# smd_2.net
KiCad netlist of a schematic drawn in EAGLE
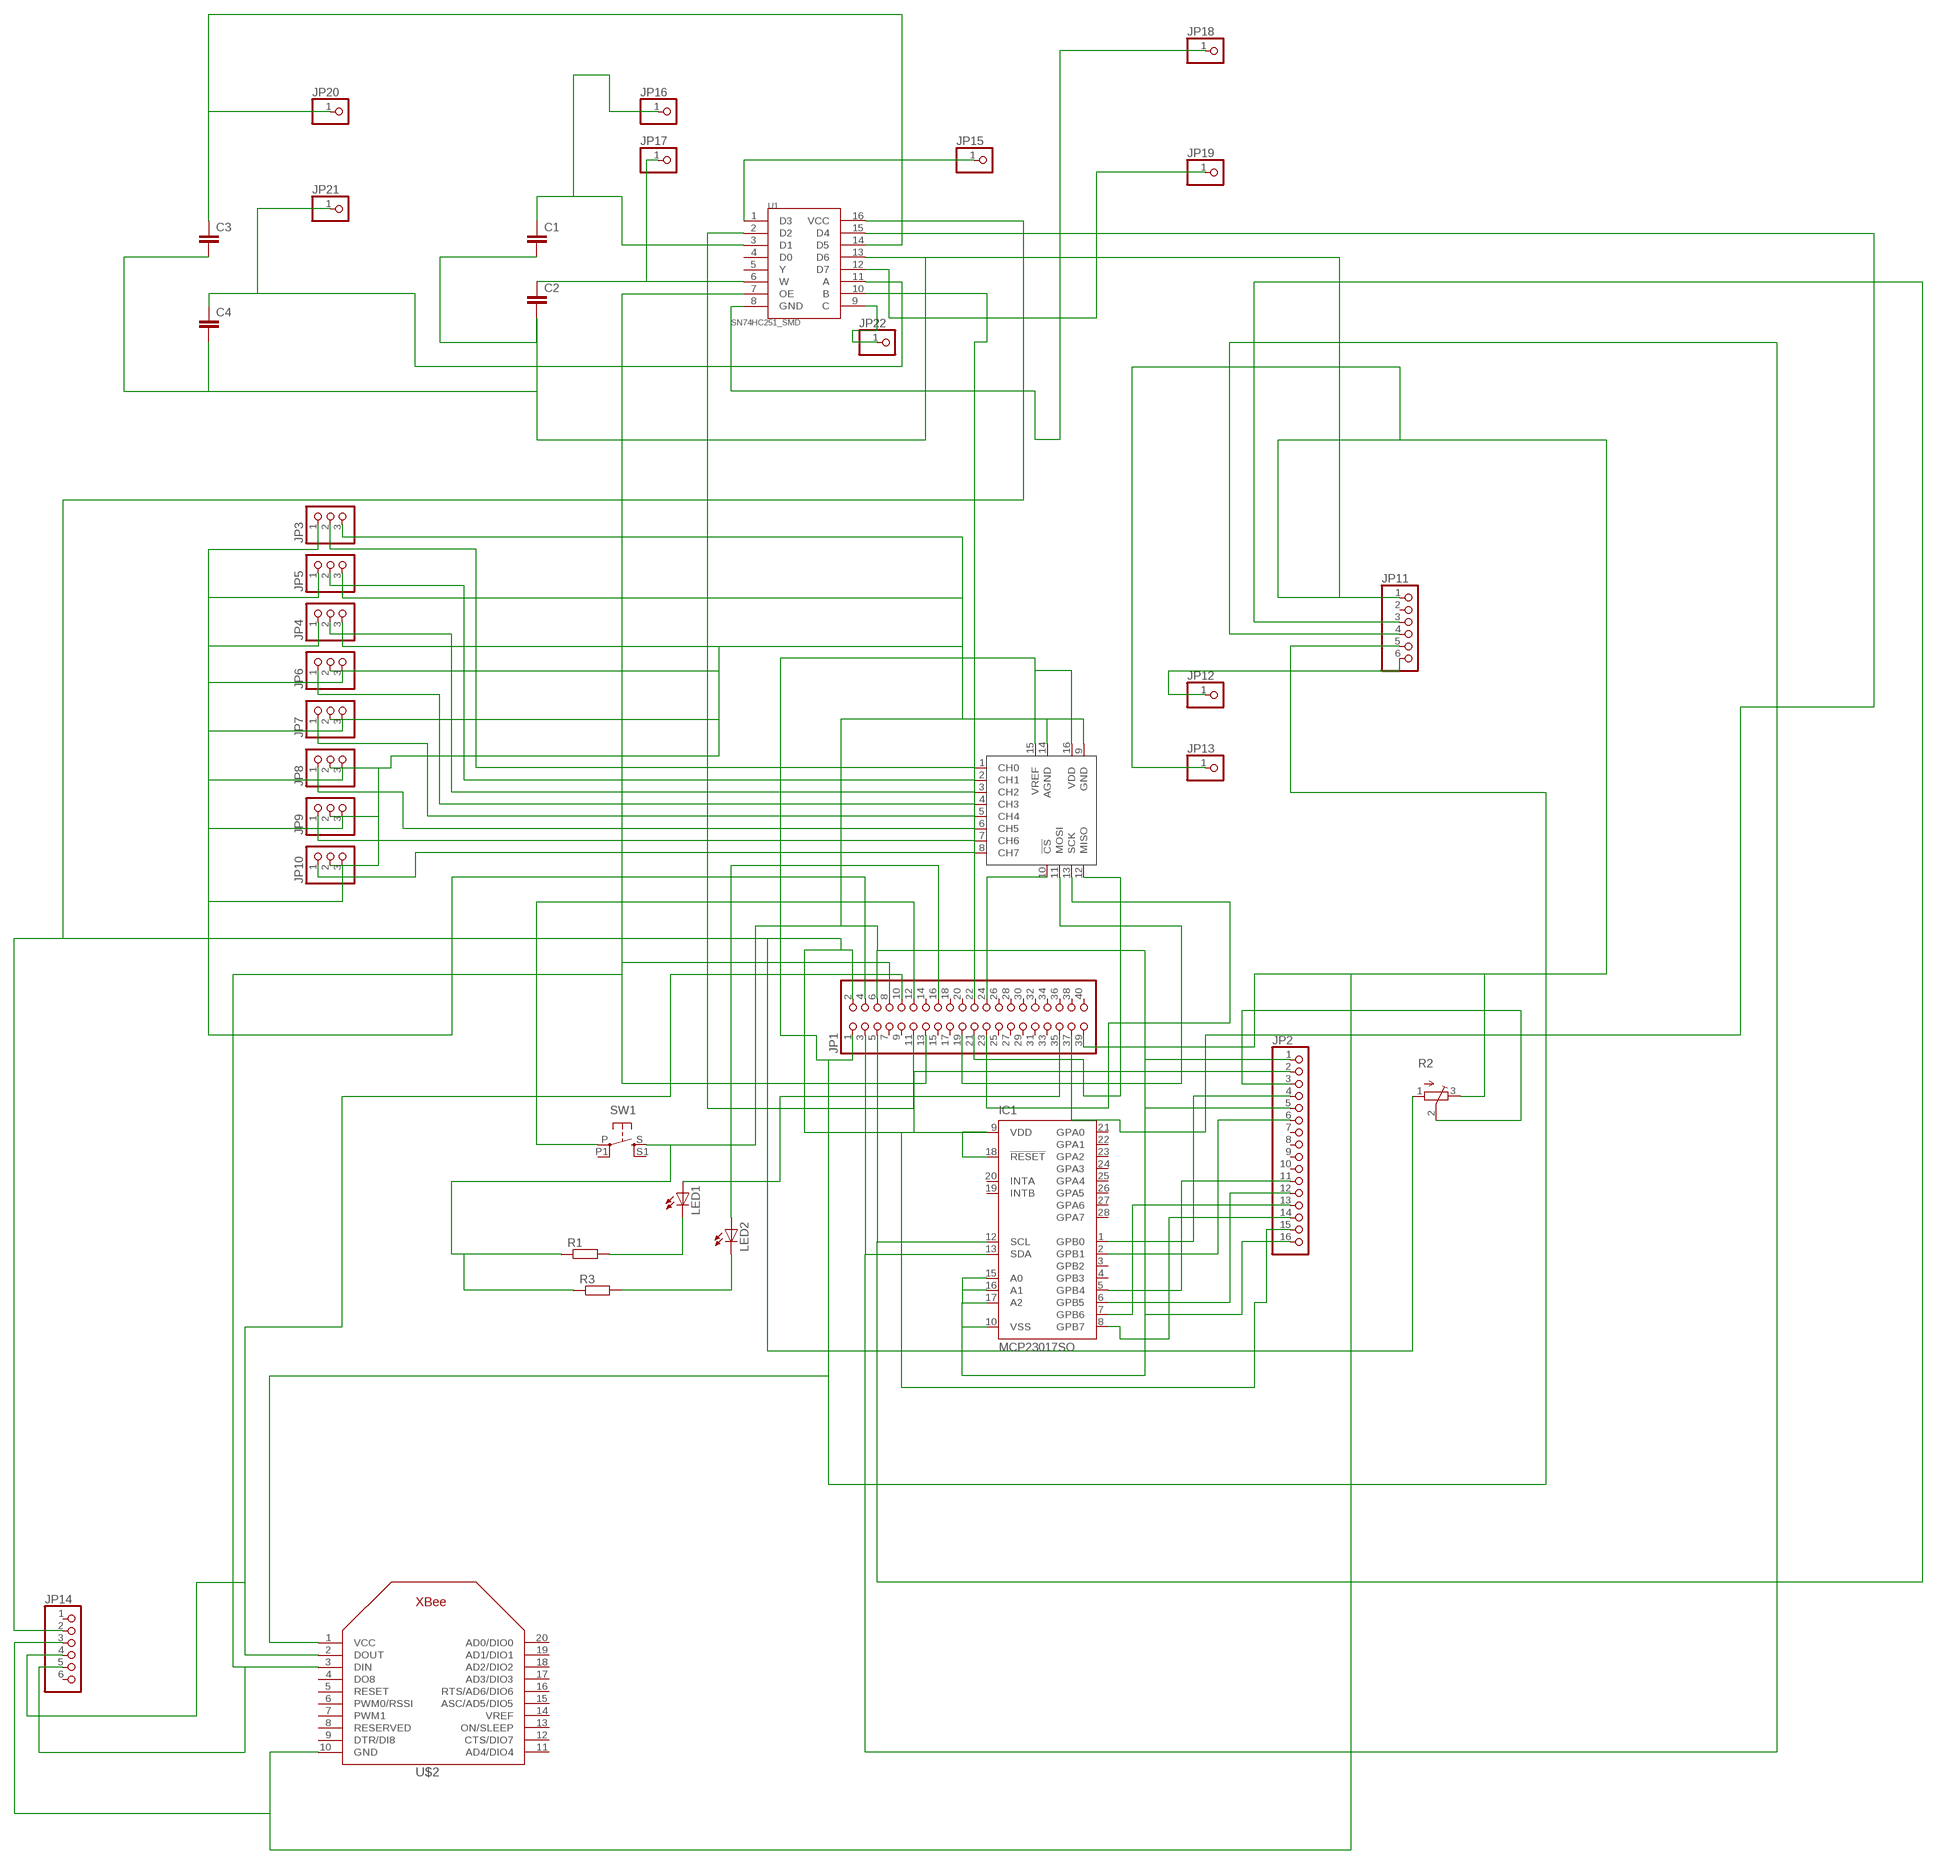
[diagram p0: schematic, sheet 1]

(export (version "E")
  (design (tool "Eeschema 10.0.6"))
  (components
    (comp (ref "C1")
      (value "CAP1206")
      (footprint "eagle-import:1206")
      (libsource (lib "eagle-import") (part "CAP1206"))
    )
    (comp (ref "C2")
      (value "CAP1206")
      (footprint "eagle-import:1206")
      (libsource (lib "eagle-import") (part "CAP1206"))
    )
    (comp (ref "C3")
      (value "CAP1206")
      (footprint "eagle-import:1206")
      (libsource (lib "eagle-import") (part "CAP1206"))
    )
    (comp (ref "C4")
      (value "CAP1206")
      (footprint "eagle-import:1206")
      (libsource (lib "eagle-import") (part "CAP1206"))
    )
    (comp (ref "IC1")
      (value "MCP23017SO")
      (footprint "eagle-import:SO28W")
      (libsource (lib "eagle-import") (part "MCP23017SO"))
    )
    (comp (ref "JP1")
      (value "PINHD-2X20")
      (footprint "eagle-import:2X20")
      (libsource (lib "eagle-import") (part "PINHD-2X20"))
    )
    (comp (ref "JP2")
      (value "PINHD-1X16")
      (footprint "eagle-import:1X16")
      (libsource (lib "eagle-import") (part "PINHD-1X16"))
    )
    (comp (ref "JP3")
      (value "PINHD-1X3")
      (footprint "eagle-import:1X03")
      (libsource (lib "eagle-import") (part "PINHD-1X3"))
    )
    (comp (ref "JP4")
      (value "PINHD-1X3")
      (footprint "eagle-import:1X03")
      (libsource (lib "eagle-import") (part "PINHD-1X3"))
    )
    (comp (ref "JP5")
      (value "PINHD-1X3")
      (footprint "eagle-import:1X03")
      (libsource (lib "eagle-import") (part "PINHD-1X3"))
    )
    (comp (ref "JP6")
      (value "PINHD-1X3")
      (footprint "eagle-import:1X03")
      (libsource (lib "eagle-import") (part "PINHD-1X3"))
    )
    (comp (ref "JP7")
      (value "PINHD-1X3")
      (footprint "eagle-import:1X03")
      (libsource (lib "eagle-import") (part "PINHD-1X3"))
    )
    (comp (ref "JP8")
      (value "PINHD-1X3")
      (footprint "eagle-import:1X03")
      (libsource (lib "eagle-import") (part "PINHD-1X3"))
    )
    (comp (ref "JP9")
      (value "PINHD-1X3")
      (footprint "eagle-import:1X03")
      (libsource (lib "eagle-import") (part "PINHD-1X3"))
    )
    (comp (ref "JP10")
      (value "PINHD-1X3")
      (footprint "eagle-import:1X03")
      (libsource (lib "eagle-import") (part "PINHD-1X3"))
    )
    (comp (ref "JP11")
      (value "PINHD-1X6")
      (footprint "eagle-import:1X06")
      (libsource (lib "eagle-import") (part "PINHD-1X6"))
    )
    (comp (ref "JP12")
      (value "PINHD-1X1")
      (footprint "eagle-import:1X01")
      (libsource (lib "eagle-import") (part "PINHD-1X1"))
    )
    (comp (ref "JP13")
      (value "PINHD-1X1")
      (footprint "eagle-import:1X01")
      (libsource (lib "eagle-import") (part "PINHD-1X1"))
    )
    (comp (ref "JP14")
      (value "PINHD-1X6")
      (footprint "eagle-import:1X06")
      (libsource (lib "eagle-import") (part "PINHD-1X6"))
    )
    (comp (ref "JP15")
      (value "PINHD-1X1")
      (footprint "eagle-import:1X01")
      (libsource (lib "eagle-import") (part "PINHD-1X1"))
    )
    (comp (ref "JP16")
      (value "PINHD-1X1")
      (footprint "eagle-import:1X01")
      (libsource (lib "eagle-import") (part "PINHD-1X1"))
    )
    (comp (ref "JP17")
      (value "PINHD-1X1")
      (footprint "eagle-import:1X01")
      (libsource (lib "eagle-import") (part "PINHD-1X1"))
    )
    (comp (ref "JP18")
      (value "PINHD-1X1")
      (footprint "eagle-import:1X01")
      (libsource (lib "eagle-import") (part "PINHD-1X1"))
    )
    (comp (ref "JP19")
      (value "PINHD-1X1")
      (footprint "eagle-import:1X01")
      (libsource (lib "eagle-import") (part "PINHD-1X1"))
    )
    (comp (ref "JP20")
      (value "PINHD-1X1")
      (footprint "eagle-import:1X01")
      (libsource (lib "eagle-import") (part "PINHD-1X1"))
    )
    (comp (ref "JP21")
      (value "PINHD-1X1")
      (footprint "eagle-import:1X01")
      (libsource (lib "eagle-import") (part "PINHD-1X1"))
    )
    (comp (ref "JP22")
      (value "PINHD-1X1")
      (footprint "eagle-import:1X01")
      (libsource (lib "eagle-import") (part "PINHD-1X1"))
    )
    (comp (ref "LED1")
      (value "LEDSMT1206")
      (footprint "eagle-import:1206")
      (libsource (lib "eagle-import") (part "LEDSMT1206"))
    )
    (comp (ref "LED2")
      (value "LEDCHIPLED_1206")
      (footprint "eagle-import:CHIPLED_1206")
      (libsource (lib "eagle-import") (part "LEDCHIPLED_1206"))
    )
    (comp (ref "R1")
      (value "R-EU_M1206")
      (footprint "eagle-import:M1206")
      (libsource (lib "eagle-import") (part "R-EU_M1206"))
    )
    (comp (ref "R2")
      (value "TRIM_EU-3223W")
      (footprint "eagle-import:3223W")
      (libsource (lib "eagle-import") (part "TRIM_EU-3223W"))
    )
    (comp (ref "R3")
      (value "R-EU_M1206")
      (footprint "eagle-import:M1206")
      (libsource (lib "eagle-import") (part "R-EU_M1206"))
    )
    (comp (ref "SW1")
      (value "10-XX-4.5SMD")
      (footprint "eagle-import:BT4.5X4.5")
      (libsource (lib "eagle-import") (part "10-XX-4.5SMD"))
    )
    (comp (ref "U$1")
      (value "MCP3008SL")
      (footprint "eagle-import:SO16")
      (libsource (lib "eagle-import") (part "MCP3008SL"))
    )
    (comp (ref "U$2")
      (value "XBEE")
      (footprint "eagle-import:XBEE")
      (libsource (lib "eagle-import") (part "XBEE"))
    )
    (comp (ref "U1")
      (value "SN74HC251_SMD")
      (footprint "eagle-import:SO016")
      (libsource (lib "eagle-import") (part "SN74HC251_SMD"))
    )
  )
  (nets
    (net (code "1") (name "Net-(IC1-A0)") (class "Default")
      (node (ref "IC1") (pin "10") (pinfunction "VSS_10") (pintype "power_in"))
      (node (ref "IC1") (pin "15") (pinfunction "A0_15") (pintype "input"))
      (node (ref "IC1") (pin "16") (pinfunction "A1_16") (pintype "input"))
      (node (ref "IC1") (pin "17") (pinfunction "A2_17") (pintype "input"))
      (node (ref "JP1") (pin "6") (pinfunction "6_6") (pintype "passive"))
      (node (ref "JP10") (pin "2") (pinfunction "2_2") (pintype "passive"))
      (node (ref "JP2") (pin "1") (pinfunction "1_1") (pintype "passive"))
      (node (ref "JP2") (pin "16") (pinfunction "16_16") (pintype "passive"))
      (node (ref "JP2") (pin "5") (pinfunction "5_5") (pintype "passive"))
      (node (ref "JP3") (pin "3") (pinfunction "3_3") (pintype "passive"))
      (node (ref "JP4") (pin "3") (pinfunction "3_3") (pintype "passive"))
      (node (ref "JP5") (pin "3") (pinfunction "3_3") (pintype "passive"))
      (node (ref "JP6") (pin "2") (pinfunction "2_2") (pintype "passive"))
      (node (ref "JP7") (pin "2") (pinfunction "2_2") (pintype "passive"))
      (node (ref "JP8") (pin "2") (pinfunction "2_2") (pintype "passive"))
      (node (ref "JP9") (pin "2") (pinfunction "2_2") (pintype "passive"))
      (node (ref "R1") (pin "1") (pinfunction "1_1") (pintype "passive"))
      (node (ref "R3") (pin "1") (pinfunction "1_1") (pintype "passive"))
      (node (ref "SW1") (pin "S") (pinfunction "S_S") (pintype "passive"))
      (node (ref "U$1") (pin "14") (pinfunction "AGND_14") (pintype "power_in"))
      (node (ref "U$1") (pin "9") (pinfunction "GND_9") (pintype "power_in"))
    )
    (net (code "2") (name "Net-(IC1-GPB0)") (class "Default")
      (node (ref "IC1") (pin "1") (pinfunction "GPB0_1") (pintype "bidirectional"))
      (node (ref "JP2") (pin "4") (pinfunction "4_4") (pintype "passive"))
    )
    (net (code "3") (name "Net-(IC1-GPB1)") (class "Default")
      (node (ref "IC1") (pin "2") (pinfunction "GPB1_2") (pintype "bidirectional"))
      (node (ref "JP2") (pin "6") (pinfunction "6_6") (pintype "passive"))
    )
    (net (code "4") (name "Net-(IC1-GPB4)") (class "Default")
      (node (ref "IC1") (pin "5") (pinfunction "GPB4_5") (pintype "bidirectional"))
      (node (ref "JP2") (pin "11") (pinfunction "11_11") (pintype "passive"))
    )
    (net (code "5") (name "Net-(IC1-GPB5)") (class "Default")
      (node (ref "IC1") (pin "6") (pinfunction "GPB5_6") (pintype "bidirectional"))
      (node (ref "JP2") (pin "12") (pinfunction "12_12") (pintype "passive"))
    )
    (net (code "6") (name "Net-(IC1-GPB6)") (class "Default")
      (node (ref "IC1") (pin "7") (pinfunction "GPB6_7") (pintype "bidirectional"))
      (node (ref "JP2") (pin "13") (pinfunction "13_13") (pintype "passive"))
    )
    (net (code "7") (name "Net-(IC1-GPB7)") (class "Default")
      (node (ref "IC1") (pin "8") (pinfunction "GPB7_8") (pintype "bidirectional"))
      (node (ref "JP2") (pin "14") (pinfunction "14_14") (pintype "passive"))
    )
    (net (code "8") (name "Net-(IC1-SCL)") (class "Default")
      (node (ref "IC1") (pin "12") (pinfunction "SCL_12") (pintype "input"))
      (node (ref "JP1") (pin "5") (pinfunction "5_5") (pintype "passive"))
      (node (ref "JP11") (pin "3") (pinfunction "3_3") (pintype "passive"))
    )
    (net (code "9") (name "Net-(IC1-SDA)") (class "Default")
      (node (ref "IC1") (pin "13") (pinfunction "SDA_13") (pintype "bidirectional"))
      (node (ref "JP1") (pin "3") (pinfunction "3_3") (pintype "passive"))
      (node (ref "JP11") (pin "4") (pinfunction "4_4") (pintype "passive"))
    )
    (net (code "10") (name "Net-(IC1-VDD)") (class "Default")
      (node (ref "IC1") (pin "18") (pinfunction "~{RESET}_18") (pintype "input"))
      (node (ref "IC1") (pin "9") (pinfunction "VDD_9") (pintype "power_in"))
      (node (ref "JP1") (pin "2") (pinfunction "2_2") (pintype "passive"))
      (node (ref "JP14") (pin "2") (pinfunction "2_2") (pintype "passive"))
      (node (ref "JP2") (pin "15") (pinfunction "15_15") (pintype "passive"))
      (node (ref "JP2") (pin "2") (pinfunction "2_2") (pintype "passive"))
      (node (ref "R2") (pin "1") (pinfunction "A_1") (pintype "passive"))
      (node (ref "U1") (pin "16") (pinfunction "VCC_16") (pintype "bidirectional"))
    )
    (net (code "11") (name "Net-(JP1-Pad4)") (class "Default")
      (node (ref "JP1") (pin "4") (pinfunction "4_4") (pintype "passive"))
      (node (ref "JP10") (pin "3") (pinfunction "3_3") (pintype "passive"))
      (node (ref "JP3") (pin "1") (pinfunction "1_1") (pintype "passive"))
      (node (ref "JP4") (pin "1") (pinfunction "1_1") (pintype "passive"))
      (node (ref "JP5") (pin "1") (pinfunction "1_1") (pintype "passive"))
      (node (ref "JP6") (pin "3") (pinfunction "3_3") (pintype "passive"))
      (node (ref "JP7") (pin "3") (pinfunction "3_3") (pintype "passive"))
      (node (ref "JP8") (pin "3") (pinfunction "3_3") (pintype "passive"))
      (node (ref "JP9") (pin "3") (pinfunction "3_3") (pintype "passive"))
    )
    (net (code "12") (name "Net-(JP1-Pad12)") (class "Default")
      (node (ref "JP1") (pin "12") (pinfunction "12_12") (pintype "passive"))
      (node (ref "SW1") (pin "P") (pinfunction "P_P") (pintype "passive"))
    )
    (net (code "13") (name "Net-(JP1-Pad16)") (class "Default")
      (node (ref "JP1") (pin "16") (pinfunction "16_16") (pintype "passive"))
      (node (ref "LED2") (pin "A") (pinfunction "A_A") (pintype "passive"))
    )
    (net (code "14") (name "Net-(JP1-Pad35)") (class "Default")
      (node (ref "JP1") (pin "35") (pinfunction "35_35") (pintype "passive"))
      (node (ref "LED1") (pin "A") (pinfunction "A_A") (pintype "passive"))
    )
    (net (code "15") (name "Net-(JP11-Pad6)") (class "Default")
      (node (ref "JP11") (pin "6") (pinfunction "6_6") (pintype "passive"))
      (node (ref "JP12") (pin "1") (pinfunction "1_1") (pintype "passive"))
    )
    (net (code "16") (name "Net-(LED1-PadC)") (class "Default")
      (node (ref "LED1") (pin "C") (pinfunction "C_C") (pintype "passive"))
      (node (ref "R1") (pin "2") (pinfunction "2_2") (pintype "passive"))
    )
    (net (code "17") (name "Net-(LED2-PadC)") (class "Default")
      (node (ref "LED2") (pin "C") (pinfunction "C_C") (pintype "passive"))
      (node (ref "R3") (pin "2") (pinfunction "2_2") (pintype "passive"))
    )
    (net (code "18") (name "Net-(R2-E)") (class "Default")
      (node (ref "C1") (pin "2") (pinfunction "2_2") (pintype "passive"))
      (node (ref "C2") (pin "2") (pinfunction "2_2") (pintype "passive"))
      (node (ref "C3") (pin "2") (pinfunction "2_2") (pintype "passive"))
      (node (ref "C4") (pin "2") (pinfunction "2_2") (pintype "passive"))
      (node (ref "JP1") (pin "39") (pinfunction "39_39") (pintype "passive"))
      (node (ref "JP11") (pin "1") (pinfunction "1_1") (pintype "passive"))
      (node (ref "JP13") (pin "1") (pinfunction "1_1") (pintype "passive"))
      (node (ref "JP14") (pin "3") (pinfunction "3_3") (pintype "passive"))
      (node (ref "R2") (pin "3") (pinfunction "E_3") (pintype "passive"))
      (node (ref "U$2") (pin "10") (pinfunction "GND_10") (pintype "power_in"))
      (node (ref "U1") (pin "13") (pinfunction "D6_13") (pintype "bidirectional"))
    )
    (net (code "19") (name "Net-(R2-S)") (class "Default")
      (node (ref "JP2") (pin "3") (pinfunction "3_3") (pintype "passive"))
      (node (ref "R2") (pin "2") (pinfunction "S_2") (pintype "passive"))
    )
    (net (code "20") (name "Net-(U$1-CH0)") (class "Default")
      (node (ref "JP3") (pin "2") (pinfunction "2_2") (pintype "passive"))
      (node (ref "U$1") (pin "1") (pinfunction "CH0_1") (pintype "input"))
    )
    (net (code "21") (name "Net-(U$1-CH1)") (class "Default")
      (node (ref "JP5") (pin "2") (pinfunction "2_2") (pintype "passive"))
      (node (ref "U$1") (pin "2") (pinfunction "CH1_2") (pintype "input"))
    )
    (net (code "22") (name "Net-(U$1-CH2)") (class "Default")
      (node (ref "JP4") (pin "2") (pinfunction "2_2") (pintype "passive"))
      (node (ref "U$1") (pin "3") (pinfunction "CH2_3") (pintype "input"))
    )
    (net (code "23") (name "Net-(U$1-CH3)") (class "Default")
      (node (ref "JP6") (pin "1") (pinfunction "1_1") (pintype "passive"))
      (node (ref "U$1") (pin "4") (pinfunction "CH3_4") (pintype "input"))
    )
    (net (code "24") (name "Net-(U$1-CH4)") (class "Default")
      (node (ref "JP7") (pin "1") (pinfunction "1_1") (pintype "passive"))
      (node (ref "U$1") (pin "5") (pinfunction "CH4_5") (pintype "input"))
    )
    (net (code "25") (name "Net-(U$1-CH5)") (class "Default")
      (node (ref "JP8") (pin "1") (pinfunction "1_1") (pintype "passive"))
      (node (ref "U$1") (pin "6") (pinfunction "CH5_6") (pintype "input"))
    )
    (net (code "26") (name "Net-(U$1-CH6)") (class "Default")
      (node (ref "JP9") (pin "1") (pinfunction "1_1") (pintype "passive"))
      (node (ref "U$1") (pin "7") (pinfunction "CH6_7") (pintype "input"))
    )
    (net (code "27") (name "Net-(U$1-CH7)") (class "Default")
      (node (ref "JP10") (pin "1") (pinfunction "1_1") (pintype "passive"))
      (node (ref "U$1") (pin "8") (pinfunction "CH7_8") (pintype "input"))
    )
    (net (code "28") (name "Net-(U$1-MISO)") (class "Default")
      (node (ref "JP1") (pin "21") (pinfunction "21_21") (pintype "passive"))
      (node (ref "U$1") (pin "12") (pinfunction "MISO_12") (pintype "output"))
    )
    (net (code "29") (name "Net-(U$1-MOSI)") (class "Default")
      (node (ref "JP1") (pin "19") (pinfunction "19_19") (pintype "passive"))
      (node (ref "U$1") (pin "11") (pinfunction "MOSI_11") (pintype "input"))
    )
    (net (code "30") (name "Net-(U$1-SCK)") (class "Default")
      (node (ref "JP1") (pin "23") (pinfunction "23_23") (pintype "passive"))
      (node (ref "U$1") (pin "13") (pinfunction "SCK_13") (pintype "input"))
    )
    (net (code "31") (name "Net-(U$1-VDD)") (class "Default")
      (node (ref "JP1") (pin "1") (pinfunction "1_1") (pintype "passive"))
      (node (ref "JP11") (pin "5") (pinfunction "5_5") (pintype "passive"))
      (node (ref "U$1") (pin "15") (pinfunction "VREF_15") (pintype "power_in"))
      (node (ref "U$1") (pin "16") (pinfunction "VDD_16") (pintype "power_in"))
      (node (ref "U$2") (pin "1") (pinfunction "VCC_1") (pintype "power_in"))
    )
    (net (code "32") (name "Net-(U$1-~{CS})") (class "Default")
      (node (ref "JP1") (pin "24") (pinfunction "24_24") (pintype "passive"))
      (node (ref "U$1") (pin "10") (pinfunction "~{CS}_10") (pintype "input"))
    )
    (net (code "33") (name "Net-(U$2-DIN)") (class "Default")
      (node (ref "JP1") (pin "8") (pinfunction "8_8") (pintype "passive"))
      (node (ref "JP14") (pin "5") (pinfunction "5_5") (pintype "passive"))
      (node (ref "U$2") (pin "3") (pinfunction "DIN_3") (pintype "input"))
    )
    (net (code "34") (name "Net-(U$2-DOUT)") (class "Default")
      (node (ref "JP1") (pin "10") (pinfunction "10_10") (pintype "passive"))
      (node (ref "JP14") (pin "4") (pinfunction "4_4") (pintype "passive"))
      (node (ref "U$2") (pin "2") (pinfunction "DOUT_2") (pintype "output"))
    )
    (net (code "35") (name "Net-(U1-A)") (class "Default")
      (node (ref "C4") (pin "1") (pinfunction "1_1") (pintype "passive"))
      (node (ref "JP21") (pin "1") (pinfunction "1_1") (pintype "passive"))
      (node (ref "U1") (pin "11") (pinfunction "A_11") (pintype "bidirectional"))
    )
    (net (code "36") (name "Net-(U1-B)") (class "Default")
      (node (ref "JP1") (pin "22") (pinfunction "22_22") (pintype "passive"))
      (node (ref "U1") (pin "10") (pinfunction "B_10") (pintype "bidirectional"))
    )
    (net (code "37") (name "Net-(U1-C)") (class "Default")
      (node (ref "JP22") (pin "1") (pinfunction "1_1") (pintype "passive"))
      (node (ref "U1") (pin "9") (pinfunction "C_9") (pintype "bidirectional"))
    )
    (net (code "38") (name "Net-(U1-D1)") (class "Default")
      (node (ref "C1") (pin "1") (pinfunction "1_1") (pintype "passive"))
      (node (ref "JP16") (pin "1") (pinfunction "1_1") (pintype "passive"))
      (node (ref "U1") (pin "3") (pinfunction "D1_3") (pintype "bidirectional"))
    )
    (net (code "39") (name "Net-(U1-D2)") (class "Default")
      (node (ref "JP1") (pin "11") (pinfunction "11_11") (pintype "passive"))
      (node (ref "U1") (pin "2") (pinfunction "D2_2") (pintype "bidirectional"))
    )
    (net (code "40") (name "Net-(U1-D3)") (class "Default")
      (node (ref "JP15") (pin "1") (pinfunction "1_1") (pintype "passive"))
      (node (ref "U1") (pin "1") (pinfunction "D3_1") (pintype "bidirectional"))
    )
    (net (code "41") (name "Net-(U1-D4)") (class "Default")
      (node (ref "JP1") (pin "37") (pinfunction "37_37") (pintype "passive"))
      (node (ref "U1") (pin "15") (pinfunction "D4_15") (pintype "bidirectional"))
    )
    (net (code "42") (name "Net-(U1-D5)") (class "Default")
      (node (ref "C3") (pin "1") (pinfunction "1_1") (pintype "passive"))
      (node (ref "JP20") (pin "1") (pinfunction "1_1") (pintype "passive"))
      (node (ref "U1") (pin "14") (pinfunction "D5_14") (pintype "bidirectional"))
    )
    (net (code "43") (name "Net-(U1-D7)") (class "Default")
      (node (ref "JP19") (pin "1") (pinfunction "1_1") (pintype "passive"))
      (node (ref "U1") (pin "12") (pinfunction "D7_12") (pintype "bidirectional"))
    )
    (net (code "44") (name "Net-(U1-GND)") (class "Default")
      (node (ref "JP18") (pin "1") (pinfunction "1_1") (pintype "passive"))
      (node (ref "U1") (pin "8") (pinfunction "GND_8") (pintype "bidirectional"))
    )
    (net (code "45") (name "Net-(U1-OE)") (class "Default")
      (node (ref "JP1") (pin "13") (pinfunction "13_13") (pintype "passive"))
      (node (ref "U1") (pin "7") (pinfunction "OE_7") (pintype "bidirectional"))
    )
    (net (code "46") (name "Net-(U1-W)") (class "Default")
      (node (ref "C2") (pin "1") (pinfunction "1_1") (pintype "passive"))
      (node (ref "JP17") (pin "1") (pinfunction "1_1") (pintype "passive"))
      (node (ref "U1") (pin "6") (pinfunction "W_6") (pintype "bidirectional"))
    )
    (net (code "47") (name "unconnected-(IC1-GPA0-Pad21)") (class "Default")
      (node (ref "IC1") (pin "21") (pinfunction "GPA0_21") (pintype "bidirectional"))
    )
    (net (code "48") (name "unconnected-(IC1-GPA1-Pad22)") (class "Default")
      (node (ref "IC1") (pin "22") (pinfunction "GPA1_22") (pintype "bidirectional"))
    )
    (net (code "49") (name "unconnected-(IC1-GPA2-Pad23)") (class "Default")
      (node (ref "IC1") (pin "23") (pinfunction "GPA2_23") (pintype "bidirectional"))
    )
    (net (code "50") (name "unconnected-(IC1-GPA3-Pad24)") (class "Default")
      (node (ref "IC1") (pin "24") (pinfunction "GPA3_24") (pintype "bidirectional"))
    )
    (net (code "51") (name "unconnected-(IC1-GPA4-Pad25)") (class "Default")
      (node (ref "IC1") (pin "25") (pinfunction "GPA4_25") (pintype "bidirectional"))
    )
    (net (code "52") (name "unconnected-(IC1-GPA5-Pad26)") (class "Default")
      (node (ref "IC1") (pin "26") (pinfunction "GPA5_26") (pintype "bidirectional"))
    )
    (net (code "53") (name "unconnected-(IC1-GPA6-Pad27)") (class "Default")
      (node (ref "IC1") (pin "27") (pinfunction "GPA6_27") (pintype "bidirectional"))
    )
    (net (code "54") (name "unconnected-(IC1-GPA7-Pad28)") (class "Default")
      (node (ref "IC1") (pin "28") (pinfunction "GPA7_28") (pintype "bidirectional"))
    )
    (net (code "55") (name "unconnected-(IC1-GPB2-Pad3)") (class "Default")
      (node (ref "IC1") (pin "3") (pinfunction "GPB2_3") (pintype "bidirectional"))
    )
    (net (code "56") (name "unconnected-(IC1-GPB3-Pad4)") (class "Default")
      (node (ref "IC1") (pin "4") (pinfunction "GPB3_4") (pintype "bidirectional"))
    )
    (net (code "57") (name "unconnected-(IC1-INTA-Pad20)") (class "Default")
      (node (ref "IC1") (pin "20") (pinfunction "INTA_20") (pintype "output"))
    )
    (net (code "58") (name "unconnected-(IC1-INTB-Pad19)") (class "Default")
      (node (ref "IC1") (pin "19") (pinfunction "INTB_19") (pintype "output"))
    )
    (net (code "59") (name "unconnected-(JP1-Pad7)") (class "Default")
      (node (ref "JP1") (pin "7") (pinfunction "7_7") (pintype "passive"))
    )
    (net (code "60") (name "unconnected-(JP1-Pad9)") (class "Default")
      (node (ref "JP1") (pin "9") (pinfunction "9_9") (pintype "passive"))
    )
    (net (code "61") (name "unconnected-(JP1-Pad14)") (class "Default")
      (node (ref "JP1") (pin "14") (pinfunction "14_14") (pintype "passive"))
    )
    (net (code "62") (name "unconnected-(JP1-Pad15)") (class "Default")
      (node (ref "JP1") (pin "15") (pinfunction "15_15") (pintype "passive"))
    )
    (net (code "63") (name "unconnected-(JP1-Pad17)") (class "Default")
      (node (ref "JP1") (pin "17") (pinfunction "17_17") (pintype "passive"))
    )
    (net (code "64") (name "unconnected-(JP1-Pad18)") (class "Default")
      (node (ref "JP1") (pin "18") (pinfunction "18_18") (pintype "passive"))
    )
    (net (code "65") (name "unconnected-(JP1-Pad20)") (class "Default")
      (node (ref "JP1") (pin "20") (pinfunction "20_20") (pintype "passive"))
    )
    (net (code "66") (name "unconnected-(JP1-Pad25)") (class "Default")
      (node (ref "JP1") (pin "25") (pinfunction "25_25") (pintype "passive"))
    )
    (net (code "67") (name "unconnected-(JP1-Pad26)") (class "Default")
      (node (ref "JP1") (pin "26") (pinfunction "26_26") (pintype "passive"))
    )
    (net (code "68") (name "unconnected-(JP1-Pad27)") (class "Default")
      (node (ref "JP1") (pin "27") (pinfunction "27_27") (pintype "passive"))
    )
    (net (code "69") (name "unconnected-(JP1-Pad28)") (class "Default")
      (node (ref "JP1") (pin "28") (pinfunction "28_28") (pintype "passive"))
    )
    (net (code "70") (name "unconnected-(JP1-Pad29)") (class "Default")
      (node (ref "JP1") (pin "29") (pinfunction "29_29") (pintype "passive"))
    )
    (net (code "71") (name "unconnected-(JP1-Pad30)") (class "Default")
      (node (ref "JP1") (pin "30") (pinfunction "30_30") (pintype "passive"))
    )
    (net (code "72") (name "unconnected-(JP1-Pad31)") (class "Default")
      (node (ref "JP1") (pin "31") (pinfunction "31_31") (pintype "passive"))
    )
    (net (code "73") (name "unconnected-(JP1-Pad32)") (class "Default")
      (node (ref "JP1") (pin "32") (pinfunction "32_32") (pintype "passive"))
    )
    (net (code "74") (name "unconnected-(JP1-Pad33)") (class "Default")
      (node (ref "JP1") (pin "33") (pinfunction "33_33") (pintype "passive"))
    )
    (net (code "75") (name "unconnected-(JP1-Pad34)") (class "Default")
      (node (ref "JP1") (pin "34") (pinfunction "34_34") (pintype "passive"))
    )
    (net (code "76") (name "unconnected-(JP1-Pad36)") (class "Default")
      (node (ref "JP1") (pin "36") (pinfunction "36_36") (pintype "passive"))
    )
    (net (code "77") (name "unconnected-(JP1-Pad38)") (class "Default")
      (node (ref "JP1") (pin "38") (pinfunction "38_38") (pintype "passive"))
    )
    (net (code "78") (name "unconnected-(JP1-Pad40)") (class "Default")
      (node (ref "JP1") (pin "40") (pinfunction "40_40") (pintype "passive"))
    )
    (net (code "79") (name "unconnected-(JP2-Pad7)") (class "Default")
      (node (ref "JP2") (pin "7") (pinfunction "7_7") (pintype "passive"))
    )
    (net (code "80") (name "unconnected-(JP2-Pad8)") (class "Default")
      (node (ref "JP2") (pin "8") (pinfunction "8_8") (pintype "passive"))
    )
    (net (code "81") (name "unconnected-(JP2-Pad9)") (class "Default")
      (node (ref "JP2") (pin "9") (pinfunction "9_9") (pintype "passive"))
    )
    (net (code "82") (name "unconnected-(JP2-Pad10)") (class "Default")
      (node (ref "JP2") (pin "10") (pinfunction "10_10") (pintype "passive"))
    )
    (net (code "83") (name "unconnected-(JP11-Pad2)") (class "Default")
      (node (ref "JP11") (pin "2") (pinfunction "2_2") (pintype "passive"))
    )
    (net (code "84") (name "unconnected-(JP14-Pad1)") (class "Default")
      (node (ref "JP14") (pin "1") (pinfunction "1_1") (pintype "passive"))
    )
    (net (code "85") (name "unconnected-(JP14-Pad6)") (class "Default")
      (node (ref "JP14") (pin "6") (pinfunction "6_6") (pintype "passive"))
    )
    (net (code "86") (name "unconnected-(SW1-PadP1)") (class "Default")
      (node (ref "SW1") (pin "P1") (pinfunction "P1_P1") (pintype "passive"))
    )
    (net (code "87") (name "unconnected-(SW1-PadS1)") (class "Default")
      (node (ref "SW1") (pin "S1") (pinfunction "S1_S1") (pintype "passive"))
    )
    (net (code "88") (name "unconnected-(U$2-AD0{slash}DIO0-Pad20)") (class "Default")
      (node (ref "U$2") (pin "20") (pinfunction "AD0/DIO0_20") (pintype "bidirectional"))
    )
    (net (code "89") (name "unconnected-(U$2-AD1{slash}DIO1-Pad19)") (class "Default")
      (node (ref "U$2") (pin "19") (pinfunction "AD1/DIO1_19") (pintype "bidirectional"))
    )
    (net (code "90") (name "unconnected-(U$2-AD2{slash}DIO2-Pad18)") (class "Default")
      (node (ref "U$2") (pin "18") (pinfunction "AD2/DIO2_18") (pintype "bidirectional"))
    )
    (net (code "91") (name "unconnected-(U$2-AD3{slash}DIO3-Pad17)") (class "Default")
      (node (ref "U$2") (pin "17") (pinfunction "AD3/DIO3_17") (pintype "bidirectional"))
    )
    (net (code "92") (name "unconnected-(U$2-AD4{slash}DIO4-Pad11)") (class "Default")
      (node (ref "U$2") (pin "11") (pinfunction "AD4/DIO4_11") (pintype "bidirectional"))
    )
    (net (code "93") (name "unconnected-(U$2-ASC{slash}AD5{slash}DIO5-Pad15)") (class "Default")
      (node (ref "U$2") (pin "15") (pinfunction "ASC/AD5/DIO5_15") (pintype "bidirectional"))
    )
    (net (code "94") (name "unconnected-(U$2-CTS{slash}DIO7-Pad12)") (class "Default")
      (node (ref "U$2") (pin "12") (pinfunction "CTS/DIO7_12") (pintype "bidirectional"))
    )
    (net (code "95") (name "unconnected-(U$2-DO8-Pad4)") (class "Default")
      (node (ref "U$2") (pin "4") (pinfunction "DO8_4") (pintype "output"))
    )
    (net (code "96") (name "unconnected-(U$2-DTR{slash}DI8-Pad9)") (class "Default")
      (node (ref "U$2") (pin "9") (pinfunction "DTR/DI8_9") (pintype "input"))
    )
    (net (code "97") (name "unconnected-(U$2-ON{slash}SLEEP-Pad13)") (class "Default")
      (node (ref "U$2") (pin "13") (pinfunction "ON/SLEEP_13") (pintype "output"))
    )
    (net (code "98") (name "unconnected-(U$2-PWM0{slash}RSSI-Pad6)") (class "Default")
      (node (ref "U$2") (pin "6") (pinfunction "PWM0/RSSI_6") (pintype "output"))
    )
    (net (code "99") (name "unconnected-(U$2-PWM1-Pad7)") (class "Default")
      (node (ref "U$2") (pin "7") (pinfunction "PWM1_7") (pintype "output"))
    )
    (net (code "100") (name "unconnected-(U$2-RESERVED-Pad8)") (class "Default")
      (node (ref "U$2") (pin "8") (pinfunction "RESERVED_8") (pintype "no_connect"))
    )
    (net (code "101") (name "unconnected-(U$2-RESET-Pad5)") (class "Default")
      (node (ref "U$2") (pin "5") (pinfunction "RESET_5") (pintype "input"))
    )
    (net (code "102") (name "unconnected-(U$2-RTS{slash}AD6{slash}DIO6-Pad16)") (class "Default")
      (node (ref "U$2") (pin "16") (pinfunction "RTS/AD6/DIO6_16") (pintype "bidirectional"))
    )
    (net (code "103") (name "unconnected-(U$2-VREF-Pad14)") (class "Default")
      (node (ref "U$2") (pin "14") (pinfunction "VREF_14") (pintype "input"))
    )
    (net (code "104") (name "unconnected-(U1-D0-Pad4)") (class "Default")
      (node (ref "U1") (pin "4") (pinfunction "D0_4") (pintype "bidirectional"))
    )
    (net (code "105") (name "unconnected-(U1-Y-Pad5)") (class "Default")
      (node (ref "U1") (pin "5") (pinfunction "Y_5") (pintype "bidirectional"))
    )
  )
)
